# Power.net
KiCad netlist of a schematic drawn in Altium Designer
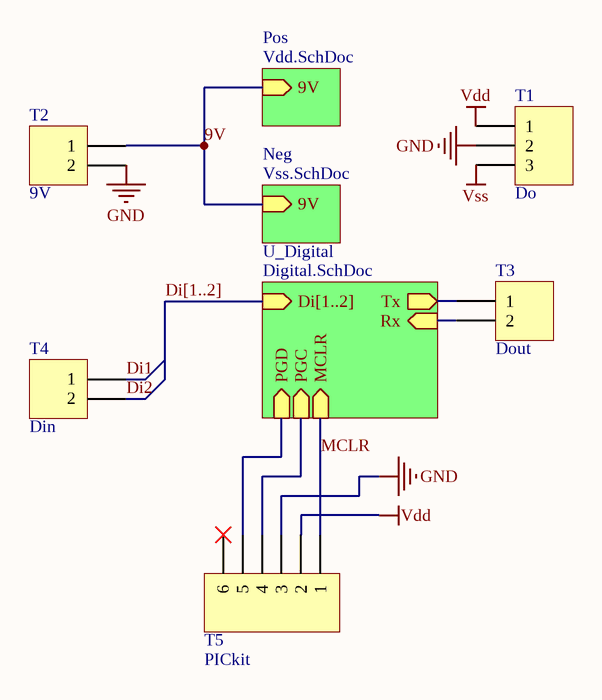
[diagram p0: Power.SchDoc]

(export (version "E")
  (design (tool "Eeschema 10.0.6"))
  (components
    (comp (ref "T1")
      (value "Do")
      (footprint "HDR1X3")
      (description "Header, 3-Pin")
      (fields (field (name "PUBLISHER") "Altium Limited"))
      (libsource (lib "Miscellaneous Connectors") (part "Header 3"))
    )
    (comp (ref "T2")
      (value "9V")
      (footprint "HDR1X2")
      (description "Header, 2-Pin")
      (fields (field (name "PUBLISHER") "Altium Limited"))
      (libsource (lib "") (part "Header 2_1"))
    )
    (comp (ref "T3")
      (value "Dout")
      (footprint "HDR1X2")
      (description "Header, 2-Pin")
      (fields (field (name "PUBLISHER") "Altium Limited"))
      (libsource (lib "Miscellaneous Connectors") (part "Header 2"))
    )
    (comp (ref "T4")
      (value "Din")
      (footprint "HDR1X2")
      (description "Header, 2-Pin")
      (fields (field (name "PUBLISHER") "Altium Limited"))
      (libsource (lib "") (part "Header 2_1"))
    )
    (comp (ref "T5")
      (value "PICkit")
      (footprint "HDR1X6")
      (description "Header, 6-Pin")
      (fields (field (name "PUBLISHER") "Altium Limited"))
      (libsource (lib "Miscellaneous Connectors") (part "Header 6"))
    )
  )
  (nets
    (net (code "1") (name "/9V") (class "Default")
      (node (ref "T2") (pin "1") (pinfunction "1_1") (pintype "passive"))
    )
    (net (code "2") (name "/Di1") (class "Default")
      (node (ref "T4") (pin "1") (pinfunction "1_1") (pintype "passive"))
    )
    (net (code "3") (name "/Di2") (class "Default")
      (node (ref "T4") (pin "2") (pinfunction "2_2") (pintype "passive"))
    )
    (net (code "5") (name "/MCLR") (class "Default")
      (node (ref "T5") (pin "1") (pinfunction "1_1") (pintype "passive"))
    )
    (net (code "6") (name "/PGC") (class "Default")
      (node (ref "T5") (pin "4") (pinfunction "4_4") (pintype "passive"))
    )
    (net (code "7") (name "/PGD") (class "Default")
      (node (ref "T5") (pin "5") (pinfunction "5_5") (pintype "passive"))
    )
    (net (code "8") (name "/Rx") (class "Default")
      (node (ref "T3") (pin "2") (pinfunction "2_2") (pintype "passive"))
    )
    (net (code "9") (name "/Tx") (class "Default")
      (node (ref "T3") (pin "1") (pinfunction "1_1") (pintype "passive"))
    )
    (net (code "10") (name "GND") (class "Default")
      (node (ref "T1") (pin "2") (pinfunction "2_2") (pintype "passive"))
      (node (ref "T2") (pin "2") (pinfunction "2_2") (pintype "passive"))
      (node (ref "T5") (pin "3") (pinfunction "3_3") (pintype "passive"))
    )
    (net (code "11") (name "Vdd") (class "Default")
      (node (ref "T1") (pin "1") (pinfunction "1_1") (pintype "passive"))
      (node (ref "T5") (pin "2") (pinfunction "2_2") (pintype "passive"))
    )
    (net (code "12") (name "Vss") (class "Default")
      (node (ref "T1") (pin "3") (pinfunction "3_3") (pintype "passive"))
    )
    (net (code "13") (name "unconnected-(T5-Pad6)") (class "Default")
      (node (ref "T5") (pin "6") (pinfunction "6_6") (pintype "passive+no_connect"))
    )
  )
)
